# table3.net
KiCad netlist of a schematic drawn in EasyEDA
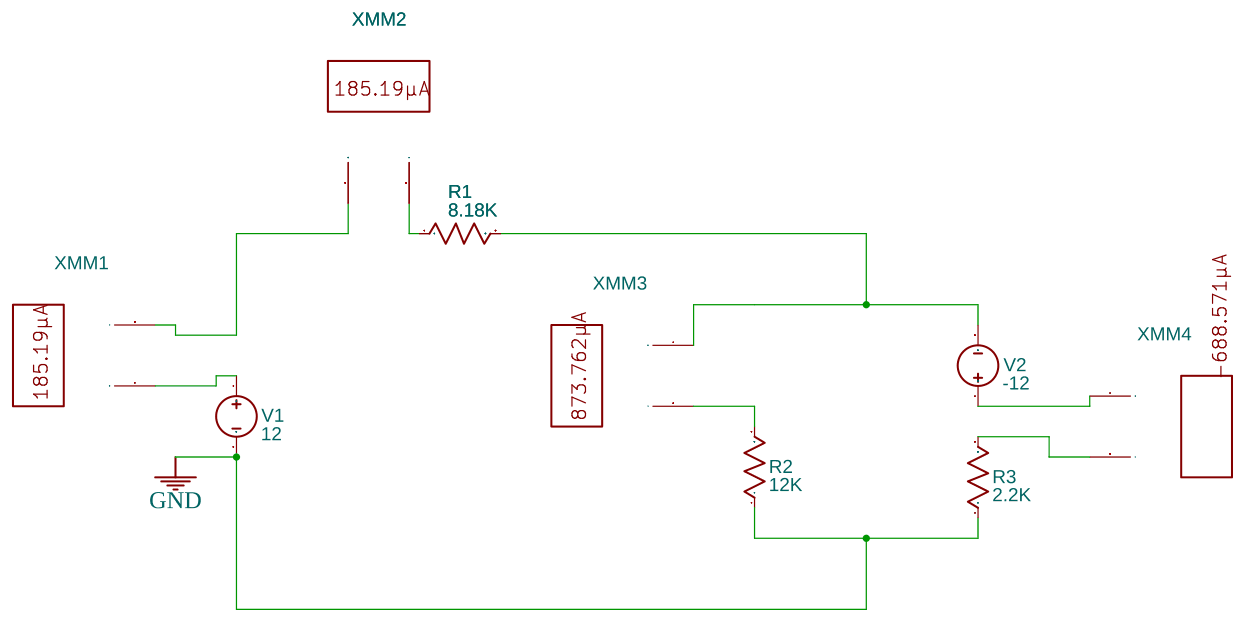
[diagram p0: schematic sheet]

(export (version "E")
  (design (tool "Eeschema 10.0.6"))
  (components
    (comp (ref "R1") (value "8.18K") (libsource (lib "") (part "Resistor_US_1")))
    (comp (ref "R2") (value "12K") (libsource (lib "") (part "Resistor_US")))
    (comp (ref "R3") (value "2.2K") (libsource (lib "") (part "Resistor_US")))
    (comp (ref "V1") (value "12") (libsource (lib "") (part "VDC_1")))
    (comp (ref "V2") (value "-12") (libsource (lib "") (part "VDC")))
    (comp (ref "XMM1") (value "Multimeter") (libsource (lib "") (part "MULTIMETER")))
    (comp (ref "XMM2") (value "Multimeter") (libsource (lib "") (part "MULTIMETER_2")))
    (comp (ref "XMM3") (value "Multimeter") (libsource (lib "") (part "MULTIMETER_3")))
    (comp (ref "XMM4") (value "Multimeter") (libsource (lib "") (part "MULTIMETER_1")))
  )
  (nets
    (net (code "1") (name "GND") (class "Default")
      (node (ref "R2") (pin "1") (pinfunction "1_1") (pintype "unspecified"))
      (node (ref "R3") (pin "1") (pinfunction "1_1") (pintype "unspecified"))
      (node (ref "V1") (pin "2") (pinfunction "2_2") (pintype "unspecified"))
    )
    (net (code "2") (name "Net-(XMM1-+)") (class "Default")
      (node (ref "V1") (pin "1") (pinfunction "1_1") (pintype "unspecified"))
      (node (ref "XMM1") (pin "1") (pinfunction "+_1") (pintype "unspecified"))
    )
    (net (code "3") (name "Net-(XMM1-I)") (class "Default")
      (node (ref "XMM1") (pin "2") (pinfunction "I_2") (pintype "unspecified"))
      (node (ref "XMM2") (pin "1") (pinfunction "+_1") (pintype "unspecified"))
    )
    (net (code "4") (name "Net-(XMM2-I)") (class "Default")
      (node (ref "R1") (pin "1") (pinfunction "1_1") (pintype "unspecified"))
      (node (ref "XMM2") (pin "2") (pinfunction "I_2") (pintype "unspecified"))
    )
    (net (code "5") (name "Net-(XMM3-+)") (class "Default")
      (node (ref "R1") (pin "2") (pinfunction "2_2") (pintype "unspecified"))
      (node (ref "V2") (pin "2") (pinfunction "2_2") (pintype "unspecified"))
      (node (ref "XMM3") (pin "1") (pinfunction "+_1") (pintype "unspecified"))
    )
    (net (code "6") (name "Net-(XMM3-I)") (class "Default")
      (node (ref "R2") (pin "2") (pinfunction "2_2") (pintype "unspecified"))
      (node (ref "XMM3") (pin "2") (pinfunction "I_2") (pintype "unspecified"))
    )
    (net (code "7") (name "Net-(XMM4-+)") (class "Default")
      (node (ref "V2") (pin "1") (pinfunction "1_1") (pintype "unspecified"))
      (node (ref "XMM4") (pin "1") (pinfunction "+_1") (pintype "unspecified"))
    )
    (net (code "8") (name "Net-(XMM4-I)") (class "Default")
      (node (ref "R3") (pin "2") (pinfunction "2_2") (pintype "unspecified"))
      (node (ref "XMM4") (pin "2") (pinfunction "I_2") (pintype "unspecified"))
    )
  )
)
